# schematic.net
KiCad netlist of a schematic drawn in EAGLE
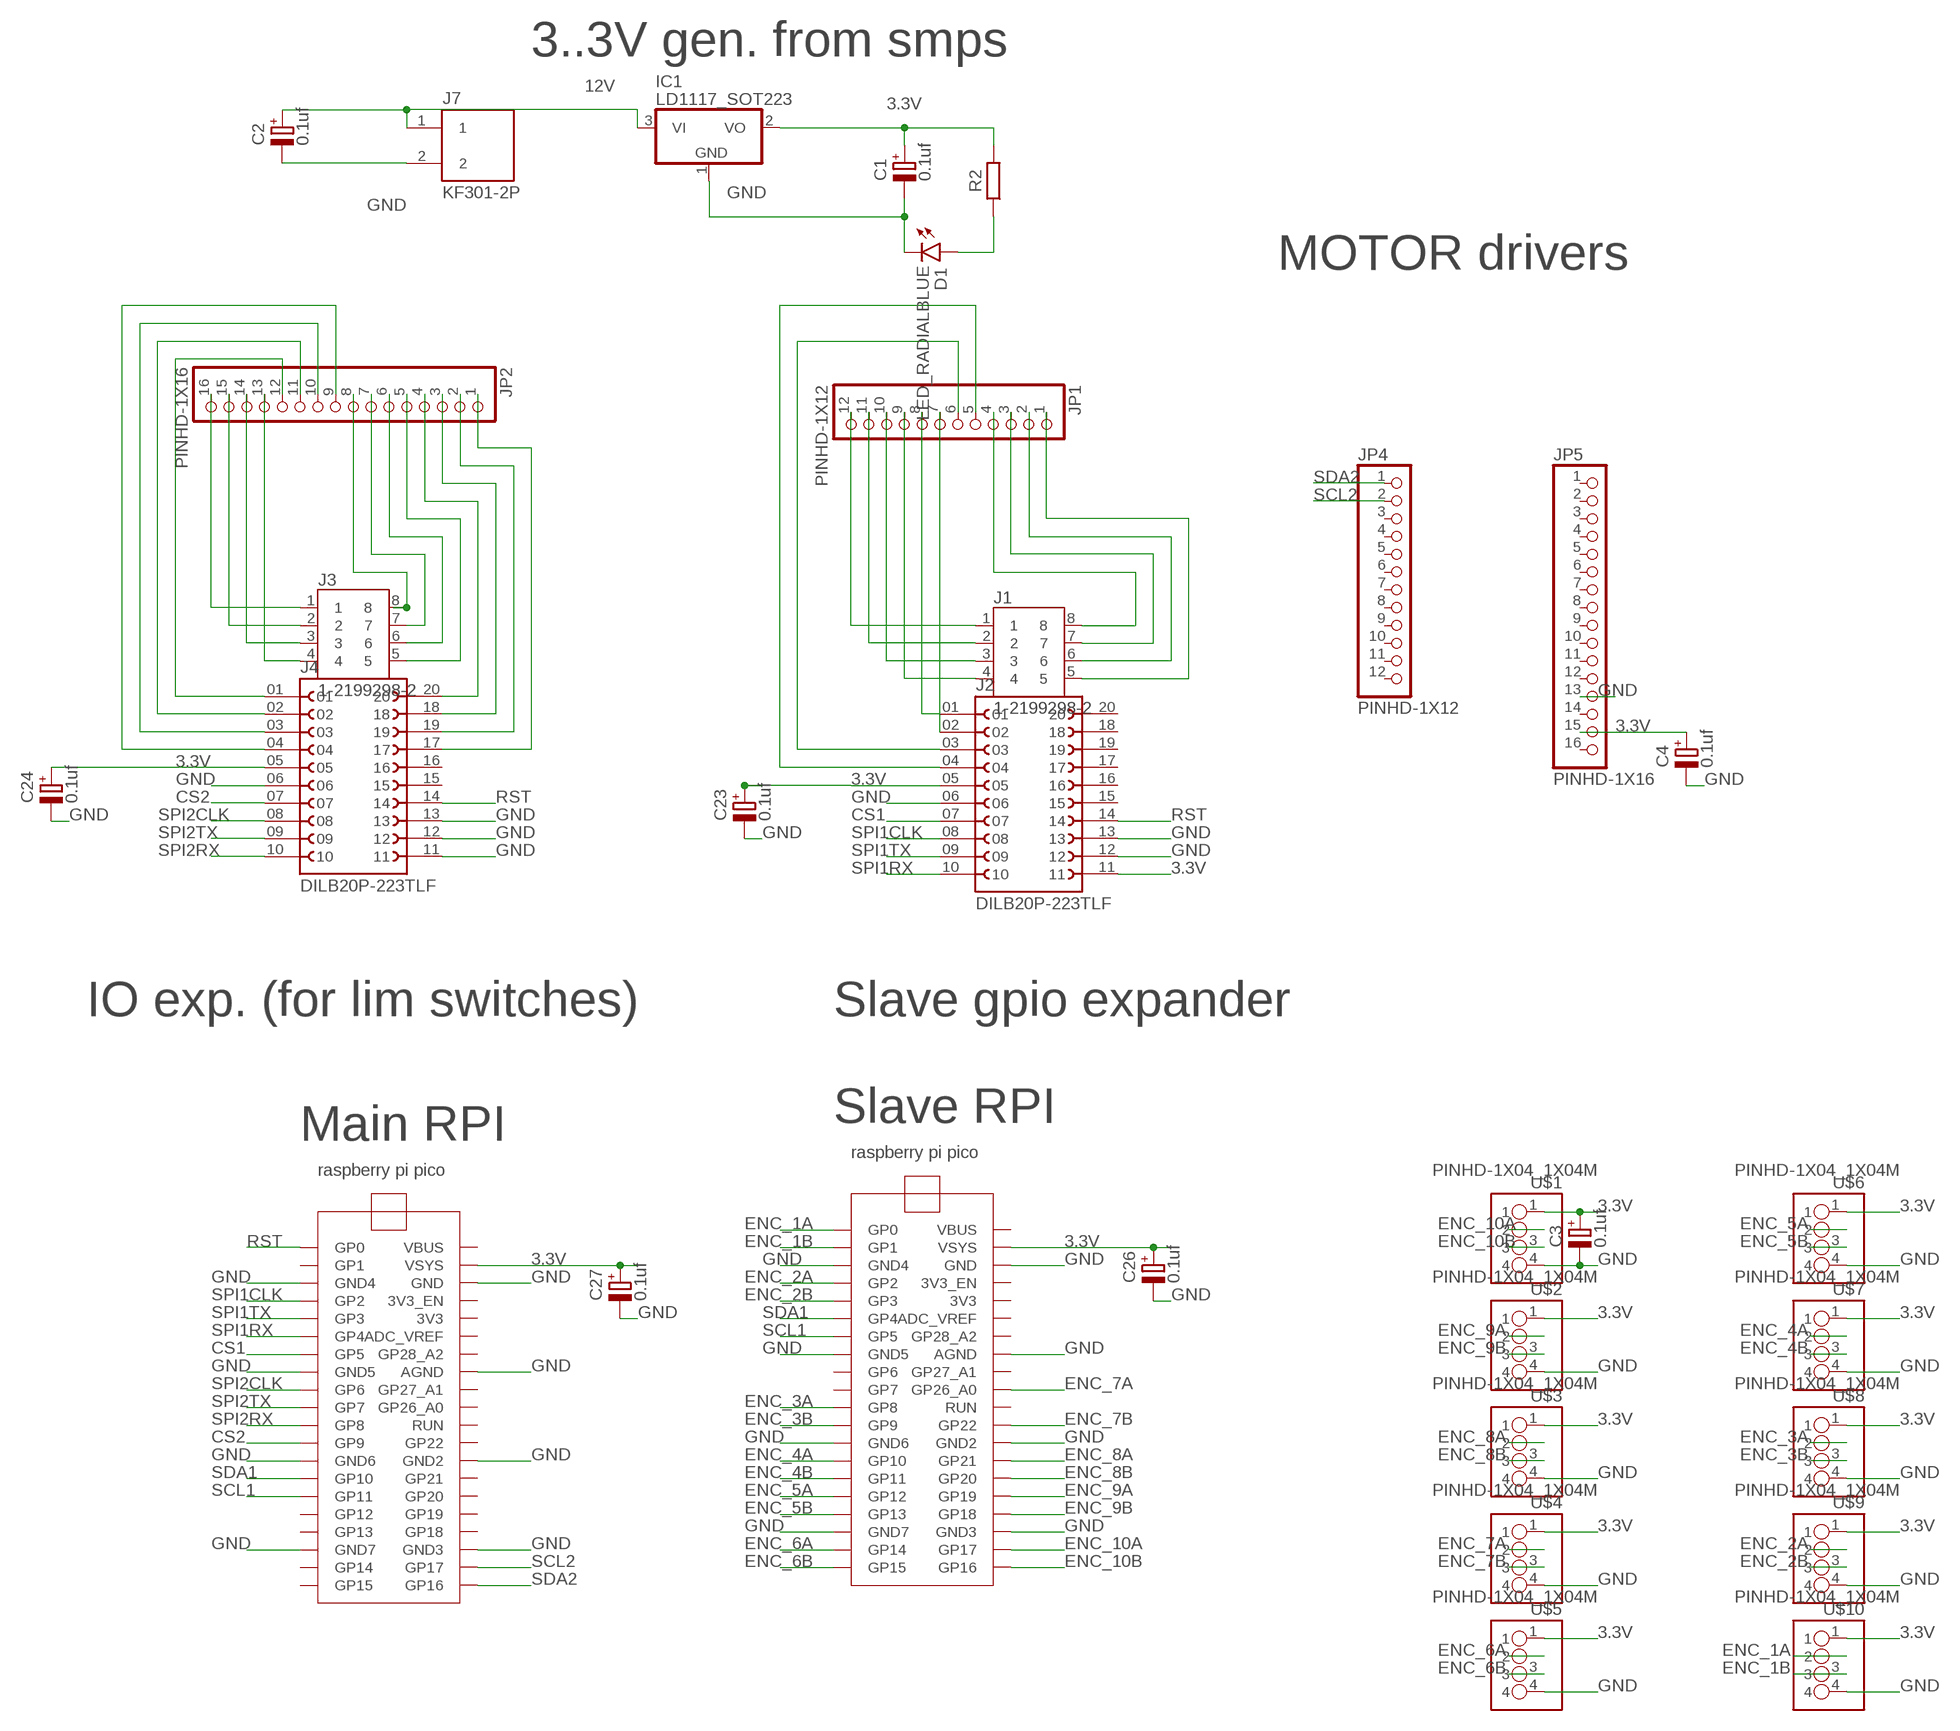
[diagram p0: schematic, sheet 1]

(export (version "E")
  (design (tool "Eeschema 10.0.6"))
  (components
    (comp (ref "C1")
      (value "0.1uf")
      (footprint "eagle-import:CAPPRD254W65D500H1150B")
      (libsource (lib "eagle-import") (part "CAPACITOR-POLRADIAL-5MM-DIA"))
    )
    (comp (ref "C2")
      (value "0.1uf")
      (footprint "eagle-import:CAPPRD254W65D500H1150B")
      (libsource (lib "eagle-import") (part "CAPACITOR-POLRADIAL-5MM-DIA"))
    )
    (comp (ref "C3")
      (value "0.1uf")
      (footprint "eagle-import:CAPPRD254W65D500H1150B")
      (libsource (lib "eagle-import") (part "CAPACITOR-POLRADIAL-5MM-DIA"))
    )
    (comp (ref "C4")
      (value "0.1uf")
      (footprint "eagle-import:CAPPRD254W65D500H1150B")
      (libsource (lib "eagle-import") (part "CAPACITOR-POLRADIAL-5MM-DIA"))
    )
    (comp (ref "C23")
      (value "0.1uf")
      (footprint "eagle-import:CAPPRD254W65D500H1150B")
      (libsource (lib "eagle-import") (part "CAPACITOR-POLRADIAL-5MM-DIA"))
    )
    (comp (ref "C24")
      (value "0.1uf")
      (footprint "eagle-import:CAPPRD254W65D500H1150B")
      (libsource (lib "eagle-import") (part "CAPACITOR-POLRADIAL-5MM-DIA"))
    )
    (comp (ref "C26")
      (value "0.1uf")
      (footprint "eagle-import:CAPPRD254W65D500H1150B")
      (libsource (lib "eagle-import") (part "CAPACITOR-POLRADIAL-5MM-DIA"))
    )
    (comp (ref "C27")
      (value "0.1uf")
      (footprint "eagle-import:CAPPRD254W65D500H1150B")
      (libsource (lib "eagle-import") (part "CAPACITOR-POLRADIAL-5MM-DIA"))
    )
    (comp (ref "D1")
      (value "LED_RADIALBLUE")
      (footprint "eagle-import:LEDRD254W60D565H860B_B")
      (libsource (lib "eagle-import") (part "LED_RADIALBLUE"))
    )
    (comp (ref "IC1")
      (value "LD1117_SOT223")
      (footprint "eagle-import:SOT230P700X170-4")
      (libsource (lib "eagle-import") (part "LD1117_SOT223"))
    )
    (comp (ref "J1")
      (value "1-2199298-2")
      (footprint "eagle-import:TE_1-2199298-2")
      (fields (field (name "MF") "TE Connectivity"))
      (libsource (lib "eagle-import") (part "1-2199298-2"))
    )
    (comp (ref "J2")
      (value "DILB20P-223TLF")
      (footprint "eagle-import:AMPHENOL_DILB20P-223TLF")
      (fields (field (name "MF") "FCI Connectors"))
      (libsource (lib "eagle-import") (part "DILB20P-223TLF"))
    )
    (comp (ref "J3")
      (value "1-2199298-2")
      (footprint "eagle-import:TE_1-2199298-2")
      (fields (field (name "MF") "TE Connectivity"))
      (libsource (lib "eagle-import") (part "1-2199298-2"))
    )
    (comp (ref "J4")
      (value "DILB20P-223TLF")
      (footprint "eagle-import:AMPHENOL_DILB20P-223TLF")
      (fields (field (name "MF") "FCI Connectors"))
      (libsource (lib "eagle-import") (part "DILB20P-223TLF"))
    )
    (comp (ref "J7")
      (value "KF301-2P")
      (footprint "eagle-import:HANDSON_KF301-2P")
      (fields (field (name "MF") "Handson Technology"))
      (libsource (lib "eagle-import") (part "KF301-2P"))
    )
    (comp (ref "JP1")
      (value "PINHD-1X12")
      (footprint "eagle-import:1X12")
      (fields (field (name "MANUFACTURER") "Generic"))
      (libsource (lib "eagle-import") (part "PINHD-1X12"))
    )
    (comp (ref "JP2")
      (value "PINHD-1X16")
      (footprint "eagle-import:1X16")
      (fields (field (name "MANUFACTURER") "Generic"))
      (libsource (lib "eagle-import") (part "PINHD-1X16"))
    )
    (comp (ref "JP4")
      (value "PINHD-1X12")
      (footprint "eagle-import:1X12")
      (fields (field (name "MANUFACTURER") "Generic"))
      (libsource (lib "eagle-import") (part "PINHD-1X12"))
    )
    (comp (ref "JP5")
      (value "PINHD-1X16")
      (footprint "eagle-import:1X16")
      (fields (field (name "MANUFACTURER") "Generic"))
      (libsource (lib "eagle-import") (part "PINHD-1X16"))
    )
    (comp (ref "R2")
      (value "R_AXIAL-11.7MM-PITCH")
      (footprint "eagle-import:RESAD1176W63L850D250B")
      (libsource (lib "eagle-import") (part "RAXIAL-11.7MM-PITCH_"))
    )
    (comp (ref "U$1")
      (value "PINHD-1X04_1X04M")
      (footprint "eagle-import:1X04")
      (libsource (lib "eagle-import") (part "PINHD-1X04_1X04M"))
    )
    (comp (ref "U$2")
      (value "PINHD-1X04_1X04M")
      (footprint "eagle-import:1X04")
      (libsource (lib "eagle-import") (part "PINHD-1X04_1X04M"))
    )
    (comp (ref "U$3")
      (value "PINHD-1X04_1X04M")
      (footprint "eagle-import:1X04")
      (libsource (lib "eagle-import") (part "PINHD-1X04_1X04M"))
    )
    (comp (ref "U$4")
      (value "PINHD-1X04_1X04M")
      (footprint "eagle-import:1X04")
      (libsource (lib "eagle-import") (part "PINHD-1X04_1X04M"))
    )
    (comp (ref "U$5")
      (value "PINHD-1X04_1X04M")
      (footprint "eagle-import:1X04")
      (libsource (lib "eagle-import") (part "PINHD-1X04_1X04M"))
    )
    (comp (ref "U$6")
      (value "PINHD-1X04_1X04M")
      (footprint "eagle-import:1X04")
      (libsource (lib "eagle-import") (part "PINHD-1X04_1X04M"))
    )
    (comp (ref "U$7")
      (value "PINHD-1X04_1X04M")
      (footprint "eagle-import:1X04")
      (libsource (lib "eagle-import") (part "PINHD-1X04_1X04M"))
    )
    (comp (ref "U$8")
      (value "PINHD-1X04_1X04M")
      (footprint "eagle-import:1X04")
      (libsource (lib "eagle-import") (part "PINHD-1X04_1X04M"))
    )
    (comp (ref "U$9")
      (value "PINHD-1X04_1X04M")
      (footprint "eagle-import:1X04")
      (libsource (lib "eagle-import") (part "PINHD-1X04_1X04M"))
    )
    (comp (ref "U$10")
      (value "PINHD-1X04_1X04M")
      (footprint "eagle-import:1X04")
      (libsource (lib "eagle-import") (part "PINHD-1X04_1X04M"))
    )
    (comp (ref "U2")
      (value "RASPBERRY_PI_PICO")
      (footprint "eagle-import:RASPBERRY_PI_PICO")
      (fields (field (name "MF") "Raspberry Pi") (field (name "MP") "RASPBERRY PI PICO"))
      (libsource (lib "eagle-import") (part "RASPBERRY_PI_PICO"))
    )
    (comp (ref "U3")
      (value "RASPBERRY_PI_PICO")
      (footprint "eagle-import:RASPBERRY_PI_PICO")
      (fields (field (name "MF") "Raspberry Pi") (field (name "MP") "RASPBERRY PI PICO"))
      (libsource (lib "eagle-import") (part "RASPBERRY_PI_PICO"))
    )
  )
  (nets
    (net (code "1") (name "/3.3V") (class "Default")
      (node (ref "C1") (pin "1") (pinfunction "+_1") (pintype "passive"))
      (node (ref "C23") (pin "1") (pinfunction "+_1") (pintype "passive"))
      (node (ref "C24") (pin "1") (pinfunction "+_1") (pintype "passive"))
      (node (ref "C26") (pin "1") (pinfunction "+_1") (pintype "passive"))
      (node (ref "C27") (pin "1") (pinfunction "+_1") (pintype "passive"))
      (node (ref "C3") (pin "1") (pinfunction "+_1") (pintype "passive"))
      (node (ref "C4") (pin "1") (pinfunction "+_1") (pintype "passive"))
      (node (ref "IC1") (pin "2") (pinfunction "VO_2") (pintype "passive"))
      (node (ref "J2") (pin "05") (pinfunction "05_05") (pintype "passive"))
      (node (ref "J2") (pin "11") (pinfunction "11_11") (pintype "passive"))
      (node (ref "J4") (pin "05") (pinfunction "05_05") (pintype "passive"))
      (node (ref "JP5") (pin "15") (pinfunction "15_15") (pintype "passive"))
      (node (ref "R2") (pin "2") (pinfunction "2_2") (pintype "passive"))
      (node (ref "U$1") (pin "1") (pinfunction "1_1") (pintype "bidirectional"))
      (node (ref "U$10") (pin "1") (pinfunction "1_1") (pintype "bidirectional"))
      (node (ref "U$2") (pin "1") (pinfunction "1_1") (pintype "bidirectional"))
      (node (ref "U$3") (pin "1") (pinfunction "1_1") (pintype "bidirectional"))
      (node (ref "U$4") (pin "1") (pinfunction "1_1") (pintype "bidirectional"))
      (node (ref "U$5") (pin "1") (pinfunction "1_1") (pintype "bidirectional"))
      (node (ref "U$6") (pin "1") (pinfunction "1_1") (pintype "bidirectional"))
      (node (ref "U$7") (pin "1") (pinfunction "1_1") (pintype "bidirectional"))
      (node (ref "U$8") (pin "1") (pinfunction "1_1") (pintype "bidirectional"))
      (node (ref "U$9") (pin "1") (pinfunction "1_1") (pintype "bidirectional"))
      (node (ref "U2") (pin "VSYS") (pinfunction "VSYS_VSYS") (pintype "bidirectional"))
      (node (ref "U3") (pin "VSYS") (pinfunction "VSYS_VSYS") (pintype "bidirectional"))
    )
    (net (code "2") (name "/12V") (class "Default")
      (node (ref "C2") (pin "1") (pinfunction "+_1") (pintype "passive"))
      (node (ref "IC1") (pin "3") (pinfunction "VI_3") (pintype "input"))
      (node (ref "J7") (pin "1") (pinfunction "1_1") (pintype "passive"))
    )
    (net (code "3") (name "/CS1") (class "Default")
      (node (ref "J2") (pin "07") (pinfunction "07_07") (pintype "passive"))
      (node (ref "U2") (pin "GP5") (pinfunction "GP5_GP5") (pintype "bidirectional"))
    )
    (net (code "4") (name "/CS2") (class "Default")
      (node (ref "J4") (pin "07") (pinfunction "07_07") (pintype "passive"))
      (node (ref "U2") (pin "GP9") (pinfunction "GP9_GP9") (pintype "bidirectional"))
    )
    (net (code "5") (name "/ENC_1A") (class "Default")
      (node (ref "U$10") (pin "2") (pinfunction "2_2") (pintype "bidirectional"))
      (node (ref "U3") (pin "GP0") (pinfunction "GP0_GP0") (pintype "bidirectional"))
    )
    (net (code "6") (name "/ENC_1B") (class "Default")
      (node (ref "U$10") (pin "3") (pinfunction "3_3") (pintype "bidirectional"))
      (node (ref "U3") (pin "GP1") (pinfunction "GP1_GP1") (pintype "bidirectional"))
    )
    (net (code "7") (name "/ENC_2A") (class "Default")
      (node (ref "U$9") (pin "2") (pinfunction "2_2") (pintype "bidirectional"))
      (node (ref "U3") (pin "GP2") (pinfunction "GP2_GP2") (pintype "bidirectional"))
    )
    (net (code "8") (name "/ENC_2B") (class "Default")
      (node (ref "U$9") (pin "3") (pinfunction "3_3") (pintype "bidirectional"))
      (node (ref "U3") (pin "GP3") (pinfunction "GP3_GP3") (pintype "bidirectional"))
    )
    (net (code "9") (name "/ENC_3A") (class "Default")
      (node (ref "U$8") (pin "2") (pinfunction "2_2") (pintype "bidirectional"))
      (node (ref "U3") (pin "GP8") (pinfunction "GP8_GP8") (pintype "bidirectional"))
    )
    (net (code "10") (name "/ENC_3B") (class "Default")
      (node (ref "U$8") (pin "3") (pinfunction "3_3") (pintype "bidirectional"))
      (node (ref "U3") (pin "GP9") (pinfunction "GP9_GP9") (pintype "bidirectional"))
    )
    (net (code "11") (name "/ENC_4A") (class "Default")
      (node (ref "U$7") (pin "2") (pinfunction "2_2") (pintype "bidirectional"))
      (node (ref "U3") (pin "GP10") (pinfunction "GP10_GP10") (pintype "bidirectional"))
    )
    (net (code "12") (name "/ENC_4B") (class "Default")
      (node (ref "U$7") (pin "3") (pinfunction "3_3") (pintype "bidirectional"))
      (node (ref "U3") (pin "GP11") (pinfunction "GP11_GP11") (pintype "bidirectional"))
    )
    (net (code "13") (name "/ENC_5A") (class "Default")
      (node (ref "U$6") (pin "2") (pinfunction "2_2") (pintype "bidirectional"))
      (node (ref "U3") (pin "GP12") (pinfunction "GP12_GP12") (pintype "bidirectional"))
    )
    (net (code "14") (name "/ENC_5B") (class "Default")
      (node (ref "U$6") (pin "3") (pinfunction "3_3") (pintype "bidirectional"))
      (node (ref "U3") (pin "GP13") (pinfunction "GP13_GP13") (pintype "bidirectional"))
    )
    (net (code "15") (name "/ENC_6A") (class "Default")
      (node (ref "U$5") (pin "2") (pinfunction "2_2") (pintype "bidirectional"))
      (node (ref "U3") (pin "GP14") (pinfunction "GP14_GP14") (pintype "bidirectional"))
    )
    (net (code "16") (name "/ENC_6B") (class "Default")
      (node (ref "U$5") (pin "3") (pinfunction "3_3") (pintype "bidirectional"))
      (node (ref "U3") (pin "GP15") (pinfunction "GP15_GP15") (pintype "bidirectional"))
    )
    (net (code "17") (name "/ENC_7A") (class "Default")
      (node (ref "U$4") (pin "2") (pinfunction "2_2") (pintype "bidirectional"))
      (node (ref "U3") (pin "GP26_A0") (pinfunction "GP26_A0_GP26_A0") (pintype "bidirectional"))
    )
    (net (code "18") (name "/ENC_7B") (class "Default")
      (node (ref "U$4") (pin "3") (pinfunction "3_3") (pintype "bidirectional"))
      (node (ref "U3") (pin "GP22") (pinfunction "GP22_GP22") (pintype "bidirectional"))
    )
    (net (code "19") (name "/ENC_8A") (class "Default")
      (node (ref "U$3") (pin "2") (pinfunction "2_2") (pintype "bidirectional"))
      (node (ref "U3") (pin "GP21") (pinfunction "GP21_GP21") (pintype "bidirectional"))
    )
    (net (code "20") (name "/ENC_8B") (class "Default")
      (node (ref "U$3") (pin "3") (pinfunction "3_3") (pintype "bidirectional"))
      (node (ref "U3") (pin "GP20") (pinfunction "GP20_GP20") (pintype "bidirectional"))
    )
    (net (code "21") (name "/ENC_9A") (class "Default")
      (node (ref "U$2") (pin "2") (pinfunction "2_2") (pintype "bidirectional"))
      (node (ref "U3") (pin "GP19") (pinfunction "GP19_GP19") (pintype "bidirectional"))
    )
    (net (code "22") (name "/ENC_9B") (class "Default")
      (node (ref "U$2") (pin "3") (pinfunction "3_3") (pintype "bidirectional"))
      (node (ref "U3") (pin "GP18") (pinfunction "GP18_GP18") (pintype "bidirectional"))
    )
    (net (code "23") (name "/ENC_10A") (class "Default")
      (node (ref "U$1") (pin "2") (pinfunction "2_2") (pintype "bidirectional"))
      (node (ref "U3") (pin "GP17") (pinfunction "GP17_GP17") (pintype "bidirectional"))
    )
    (net (code "24") (name "/ENC_10B") (class "Default")
      (node (ref "U$1") (pin "3") (pinfunction "3_3") (pintype "bidirectional"))
      (node (ref "U3") (pin "GP16") (pinfunction "GP16_GP16") (pintype "bidirectional"))
    )
    (net (code "25") (name "/GND") (class "Default")
      (node (ref "C1") (pin "2") (pinfunction "-_2") (pintype "passive"))
      (node (ref "C2") (pin "2") (pinfunction "-_2") (pintype "passive"))
      (node (ref "C23") (pin "2") (pinfunction "-_2") (pintype "passive"))
      (node (ref "C24") (pin "2") (pinfunction "-_2") (pintype "passive"))
      (node (ref "C26") (pin "2") (pinfunction "-_2") (pintype "passive"))
      (node (ref "C27") (pin "2") (pinfunction "-_2") (pintype "passive"))
      (node (ref "C3") (pin "2") (pinfunction "-_2") (pintype "passive"))
      (node (ref "C4") (pin "2") (pinfunction "-_2") (pintype "passive"))
      (node (ref "D1") (pin "C") (pinfunction "C_C") (pintype "passive"))
      (node (ref "IC1") (pin "1") (pinfunction "GND_1") (pintype "passive"))
      (node (ref "J2") (pin "06") (pinfunction "06_06") (pintype "passive"))
      (node (ref "J2") (pin "12") (pinfunction "12_12") (pintype "passive"))
      (node (ref "J2") (pin "13") (pinfunction "13_13") (pintype "passive"))
      (node (ref "J4") (pin "06") (pinfunction "06_06") (pintype "passive"))
      (node (ref "J4") (pin "11") (pinfunction "11_11") (pintype "passive"))
      (node (ref "J4") (pin "12") (pinfunction "12_12") (pintype "passive"))
      (node (ref "J4") (pin "13") (pinfunction "13_13") (pintype "passive"))
      (node (ref "J7") (pin "2") (pinfunction "2_2") (pintype "passive"))
      (node (ref "JP5") (pin "13") (pinfunction "13_13") (pintype "passive"))
      (node (ref "U$1") (pin "4") (pinfunction "4_4") (pintype "bidirectional"))
      (node (ref "U$10") (pin "4") (pinfunction "4_4") (pintype "bidirectional"))
      (node (ref "U$2") (pin "4") (pinfunction "4_4") (pintype "bidirectional"))
      (node (ref "U$3") (pin "4") (pinfunction "4_4") (pintype "bidirectional"))
      (node (ref "U$4") (pin "4") (pinfunction "4_4") (pintype "bidirectional"))
      (node (ref "U$5") (pin "4") (pinfunction "4_4") (pintype "bidirectional"))
      (node (ref "U$6") (pin "4") (pinfunction "4_4") (pintype "bidirectional"))
      (node (ref "U$7") (pin "4") (pinfunction "4_4") (pintype "bidirectional"))
      (node (ref "U$8") (pin "4") (pinfunction "4_4") (pintype "bidirectional"))
      (node (ref "U$9") (pin "4") (pinfunction "4_4") (pintype "bidirectional"))
      (node (ref "U2") (pin "AGND") (pinfunction "AGND_AGND") (pintype "bidirectional"))
      (node (ref "U2") (pin "GND") (pinfunction "GND_GND") (pintype "bidirectional"))
      (node (ref "U2") (pin "GND2") (pinfunction "GND2_GND2") (pintype "bidirectional"))
      (node (ref "U2") (pin "GND3") (pinfunction "GND3_GND3") (pintype "bidirectional"))
      (node (ref "U2") (pin "GND4") (pinfunction "GND4_GND4") (pintype "bidirectional"))
      (node (ref "U2") (pin "GND5") (pinfunction "GND5_GND5") (pintype "bidirectional"))
      (node (ref "U2") (pin "GND6") (pinfunction "GND6_GND6") (pintype "bidirectional"))
      (node (ref "U2") (pin "GND7") (pinfunction "GND7_GND7") (pintype "bidirectional"))
      (node (ref "U3") (pin "AGND") (pinfunction "AGND_AGND") (pintype "bidirectional"))
      (node (ref "U3") (pin "GND") (pinfunction "GND_GND") (pintype "bidirectional"))
      (node (ref "U3") (pin "GND2") (pinfunction "GND2_GND2") (pintype "bidirectional"))
      (node (ref "U3") (pin "GND3") (pinfunction "GND3_GND3") (pintype "bidirectional"))
      (node (ref "U3") (pin "GND4") (pinfunction "GND4_GND4") (pintype "bidirectional"))
      (node (ref "U3") (pin "GND5") (pinfunction "GND5_GND5") (pintype "bidirectional"))
      (node (ref "U3") (pin "GND6") (pinfunction "GND6_GND6") (pintype "bidirectional"))
      (node (ref "U3") (pin "GND7") (pinfunction "GND7_GND7") (pintype "bidirectional"))
    )
    (net (code "26") (name "/RST") (class "Default")
      (node (ref "J2") (pin "14") (pinfunction "14_14") (pintype "passive"))
      (node (ref "J4") (pin "14") (pinfunction "14_14") (pintype "passive"))
      (node (ref "U2") (pin "GP0") (pinfunction "GP0_GP0") (pintype "bidirectional"))
    )
    (net (code "27") (name "/SCL1") (class "Default")
      (node (ref "U2") (pin "GP11") (pinfunction "GP11_GP11") (pintype "bidirectional"))
      (node (ref "U3") (pin "GP5") (pinfunction "GP5_GP5") (pintype "bidirectional"))
    )
    (net (code "28") (name "/SCL2") (class "Default")
      (node (ref "JP4") (pin "2") (pinfunction "2_2") (pintype "passive"))
      (node (ref "U2") (pin "GP17") (pinfunction "GP17_GP17") (pintype "bidirectional"))
    )
    (net (code "29") (name "/SDA1") (class "Default")
      (node (ref "U2") (pin "GP10") (pinfunction "GP10_GP10") (pintype "bidirectional"))
      (node (ref "U3") (pin "GP4") (pinfunction "GP4_GP4") (pintype "bidirectional"))
    )
    (net (code "30") (name "/SDA2") (class "Default")
      (node (ref "JP4") (pin "1") (pinfunction "1_1") (pintype "passive"))
      (node (ref "U2") (pin "GP16") (pinfunction "GP16_GP16") (pintype "bidirectional"))
    )
    (net (code "31") (name "/SPI1CLK") (class "Default")
      (node (ref "J2") (pin "08") (pinfunction "08_08") (pintype "passive"))
      (node (ref "U2") (pin "GP2") (pinfunction "GP2_GP2") (pintype "bidirectional"))
    )
    (net (code "32") (name "/SPI1RX") (class "Default")
      (node (ref "J2") (pin "10") (pinfunction "10_10") (pintype "passive"))
      (node (ref "U2") (pin "GP4") (pinfunction "GP4_GP4") (pintype "bidirectional"))
    )
    (net (code "33") (name "/SPI1TX") (class "Default")
      (node (ref "J2") (pin "09") (pinfunction "09_09") (pintype "passive"))
      (node (ref "U2") (pin "GP3") (pinfunction "GP3_GP3") (pintype "bidirectional"))
    )
    (net (code "34") (name "/SPI2CLK") (class "Default")
      (node (ref "J4") (pin "08") (pinfunction "08_08") (pintype "passive"))
      (node (ref "U2") (pin "GP6") (pinfunction "GP6_GP6") (pintype "bidirectional"))
    )
    (net (code "35") (name "/SPI2RX") (class "Default")
      (node (ref "J4") (pin "10") (pinfunction "10_10") (pintype "passive"))
      (node (ref "U2") (pin "GP8") (pinfunction "GP8_GP8") (pintype "bidirectional"))
    )
    (net (code "36") (name "/SPI2TX") (class "Default")
      (node (ref "J4") (pin "09") (pinfunction "09_09") (pintype "passive"))
      (node (ref "U2") (pin "GP7") (pinfunction "GP7_GP7") (pintype "bidirectional"))
    )
    (net (code "37") (name "Net-(D1-PadA)") (class "Default")
      (node (ref "D1") (pin "A") (pinfunction "A_A") (pintype "passive"))
      (node (ref "R2") (pin "1") (pinfunction "1_1") (pintype "passive"))
    )
    (net (code "38") (name "Net-(J1-Pad1)") (class "Default")
      (node (ref "J1") (pin "1") (pinfunction "1_1") (pintype "passive"))
      (node (ref "JP1") (pin "12") (pinfunction "12_12") (pintype "passive"))
    )
    (net (code "39") (name "Net-(J1-Pad2)") (class "Default")
      (node (ref "J1") (pin "2") (pinfunction "2_2") (pintype "passive"))
      (node (ref "JP1") (pin "11") (pinfunction "11_11") (pintype "passive"))
    )
    (net (code "40") (name "Net-(J1-Pad3)") (class "Default")
      (node (ref "J1") (pin "3") (pinfunction "3_3") (pintype "passive"))
      (node (ref "JP1") (pin "10") (pinfunction "10_10") (pintype "passive"))
    )
    (net (code "41") (name "Net-(J1-Pad4)") (class "Default")
      (node (ref "J1") (pin "4") (pinfunction "4_4") (pintype "passive"))
      (node (ref "JP1") (pin "9") (pinfunction "9_9") (pintype "passive"))
    )
    (net (code "42") (name "Net-(J1-Pad5)") (class "Default")
      (node (ref "J1") (pin "5") (pinfunction "5_5") (pintype "passive"))
      (node (ref "JP1") (pin "1") (pinfunction "1_1") (pintype "passive"))
    )
    (net (code "43") (name "Net-(J1-Pad6)") (class "Default")
      (node (ref "J1") (pin "6") (pinfunction "6_6") (pintype "passive"))
      (node (ref "JP1") (pin "2") (pinfunction "2_2") (pintype "passive"))
    )
    (net (code "44") (name "Net-(J1-Pad7)") (class "Default")
      (node (ref "J1") (pin "7") (pinfunction "7_7") (pintype "passive"))
      (node (ref "JP1") (pin "3") (pinfunction "3_3") (pintype "passive"))
    )
    (net (code "45") (name "Net-(J1-Pad8)") (class "Default")
      (node (ref "J1") (pin "8") (pinfunction "8_8") (pintype "passive"))
      (node (ref "JP1") (pin "4") (pinfunction "4_4") (pintype "passive"))
    )
    (net (code "46") (name "Net-(J2-Pad01)") (class "Default")
      (node (ref "J2") (pin "01") (pinfunction "01_01") (pintype "passive"))
      (node (ref "JP1") (pin "8") (pinfunction "8_8") (pintype "passive"))
    )
    (net (code "47") (name "Net-(J2-Pad02)") (class "Default")
      (node (ref "J2") (pin "02") (pinfunction "02_02") (pintype "passive"))
      (node (ref "JP1") (pin "7") (pinfunction "7_7") (pintype "passive"))
    )
    (net (code "48") (name "Net-(J2-Pad03)") (class "Default")
      (node (ref "J2") (pin "03") (pinfunction "03_03") (pintype "passive"))
      (node (ref "JP1") (pin "6") (pinfunction "6_6") (pintype "passive"))
    )
    (net (code "49") (name "Net-(J2-Pad04)") (class "Default")
      (node (ref "J2") (pin "04") (pinfunction "04_04") (pintype "passive"))
      (node (ref "JP1") (pin "5") (pinfunction "5_5") (pintype "passive"))
    )
    (net (code "50") (name "Net-(J3-Pad1)") (class "Default")
      (node (ref "J3") (pin "1") (pinfunction "1_1") (pintype "passive"))
      (node (ref "JP2") (pin "16") (pinfunction "16_16") (pintype "passive"))
    )
    (net (code "51") (name "Net-(J3-Pad2)") (class "Default")
      (node (ref "J3") (pin "2") (pinfunction "2_2") (pintype "passive"))
      (node (ref "JP2") (pin "15") (pinfunction "15_15") (pintype "passive"))
    )
    (net (code "52") (name "Net-(J3-Pad3)") (class "Default")
      (node (ref "J3") (pin "3") (pinfunction "3_3") (pintype "passive"))
      (node (ref "JP2") (pin "14") (pinfunction "14_14") (pintype "passive"))
    )
    (net (code "53") (name "Net-(J3-Pad4)") (class "Default")
      (node (ref "J3") (pin "4") (pinfunction "4_4") (pintype "passive"))
      (node (ref "JP2") (pin "13") (pinfunction "13_13") (pintype "passive"))
    )
    (net (code "54") (name "Net-(J3-Pad5)") (class "Default")
      (node (ref "J3") (pin "5") (pinfunction "5_5") (pintype "passive"))
      (node (ref "JP2") (pin "5") (pinfunction "5_5") (pintype "passive"))
    )
    (net (code "55") (name "Net-(J3-Pad6)") (class "Default")
      (node (ref "J3") (pin "6") (pinfunction "6_6") (pintype "passive"))
      (node (ref "JP2") (pin "6") (pinfunction "6_6") (pintype "passive"))
    )
    (net (code "56") (name "Net-(J3-Pad7)") (class "Default")
      (node (ref "J3") (pin "7") (pinfunction "7_7") (pintype "passive"))
      (node (ref "JP2") (pin "7") (pinfunction "7_7") (pintype "passive"))
    )
    (net (code "57") (name "Net-(J3-Pad8)") (class "Default")
      (node (ref "J3") (pin "8") (pinfunction "8_8") (pintype "passive"))
      (node (ref "JP2") (pin "8") (pinfunction "8_8") (pintype "passive"))
    )
    (net (code "58") (name "Net-(J4-Pad01)") (class "Default")
      (node (ref "J4") (pin "01") (pinfunction "01_01") (pintype "passive"))
      (node (ref "JP2") (pin "12") (pinfunction "12_12") (pintype "passive"))
    )
    (net (code "59") (name "Net-(J4-Pad02)") (class "Default")
      (node (ref "J4") (pin "02") (pinfunction "02_02") (pintype "passive"))
      (node (ref "JP2") (pin "11") (pinfunction "11_11") (pintype "passive"))
    )
    (net (code "60") (name "Net-(J4-Pad03)") (class "Default")
      (node (ref "J4") (pin "03") (pinfunction "03_03") (pintype "passive"))
      (node (ref "JP2") (pin "10") (pinfunction "10_10") (pintype "passive"))
    )
    (net (code "61") (name "Net-(J4-Pad04)") (class "Default")
      (node (ref "J4") (pin "04") (pinfunction "04_04") (pintype "passive"))
      (node (ref "JP2") (pin "9") (pinfunction "9_9") (pintype "passive"))
    )
    (net (code "62") (name "Net-(J4-Pad17)") (class "Default")
      (node (ref "J4") (pin "17") (pinfunction "17_17") (pintype "passive"))
      (node (ref "JP2") (pin "1") (pinfunction "1_1") (pintype "passive"))
    )
    (net (code "63") (name "Net-(J4-Pad18)") (class "Default")
      (node (ref "J4") (pin "18") (pinfunction "18_18") (pintype "passive"))
      (node (ref "JP2") (pin "3") (pinfunction "3_3") (pintype "passive"))
    )
    (net (code "64") (name "Net-(J4-Pad19)") (class "Default")
      (node (ref "J4") (pin "19") (pinfunction "19_19") (pintype "passive"))
      (node (ref "JP2") (pin "2") (pinfunction "2_2") (pintype "passive"))
    )
    (net (code "65") (name "Net-(J4-Pad20)") (class "Default")
      (node (ref "J4") (pin "20") (pinfunction "20_20") (pintype "passive"))
      (node (ref "JP2") (pin "4") (pinfunction "4_4") (pintype "passive"))
    )
    (net (code "66") (name "unconnected-(J2-Pad15)") (class "Default")
      (node (ref "J2") (pin "15") (pinfunction "15_15") (pintype "passive"))
    )
    (net (code "67") (name "unconnected-(J2-Pad16)") (class "Default")
      (node (ref "J2") (pin "16") (pinfunction "16_16") (pintype "passive"))
    )
    (net (code "68") (name "unconnected-(J2-Pad17)") (class "Default")
      (node (ref "J2") (pin "17") (pinfunction "17_17") (pintype "passive"))
    )
    (net (code "69") (name "unconnected-(J2-Pad18)") (class "Default")
      (node (ref "J2") (pin "18") (pinfunction "18_18") (pintype "passive"))
    )
    (net (code "70") (name "unconnected-(J2-Pad19)") (class "Default")
      (node (ref "J2") (pin "19") (pinfunction "19_19") (pintype "passive"))
    )
    (net (code "71") (name "unconnected-(J2-Pad20)") (class "Default")
      (node (ref "J2") (pin "20") (pinfunction "20_20") (pintype "passive"))
    )
    (net (code "72") (name "unconnected-(J4-Pad15)") (class "Default")
      (node (ref "J4") (pin "15") (pinfunction "15_15") (pintype "passive"))
    )
    (net (code "73") (name "unconnected-(J4-Pad16)") (class "Default")
      (node (ref "J4") (pin "16") (pinfunction "16_16") (pintype "passive"))
    )
    (net (code "74") (name "unconnected-(JP4-Pad3)") (class "Default")
      (node (ref "JP4") (pin "3") (pinfunction "3_3") (pintype "passive"))
    )
    (net (code "75") (name "unconnected-(JP4-Pad4)") (class "Default")
      (node (ref "JP4") (pin "4") (pinfunction "4_4") (pintype "passive"))
    )
    (net (code "76") (name "unconnected-(JP4-Pad5)") (class "Default")
      (node (ref "JP4") (pin "5") (pinfunction "5_5") (pintype "passive"))
    )
    (net (code "77") (name "unconnected-(JP4-Pad6)") (class "Default")
      (node (ref "JP4") (pin "6") (pinfunction "6_6") (pintype "passive"))
    )
    (net (code "78") (name "unconnected-(JP4-Pad7)") (class "Default")
      (node (ref "JP4") (pin "7") (pinfunction "7_7") (pintype "passive"))
    )
    (net (code "79") (name "unconnected-(JP4-Pad8)") (class "Default")
      (node (ref "JP4") (pin "8") (pinfunction "8_8") (pintype "passive"))
    )
    (net (code "80") (name "unconnected-(JP4-Pad9)") (class "Default")
      (node (ref "JP4") (pin "9") (pinfunction "9_9") (pintype "passive"))
    )
    (net (code "81") (name "unconnected-(JP4-Pad10)") (class "Default")
      (node (ref "JP4") (pin "10") (pinfunction "10_10") (pintype "passive"))
    )
    (net (code "82") (name "unconnected-(JP4-Pad11)") (class "Default")
      (node (ref "JP4") (pin "11") (pinfunction "11_11") (pintype "passive"))
    )
    (net (code "83") (name "unconnected-(JP4-Pad12)") (class "Default")
      (node (ref "JP4") (pin "12") (pinfunction "12_12") (pintype "passive"))
    )
    (net (code "84") (name "unconnected-(JP5-Pad1)") (class "Default")
      (node (ref "JP5") (pin "1") (pinfunction "1_1") (pintype "passive"))
    )
    (net (code "85") (name "unconnected-(JP5-Pad2)") (class "Default")
      (node (ref "JP5") (pin "2") (pinfunction "2_2") (pintype "passive"))
    )
    (net (code "86") (name "unconnected-(JP5-Pad3)") (class "Default")
      (node (ref "JP5") (pin "3") (pinfunction "3_3") (pintype "passive"))
    )
    (net (code "87") (name "unconnected-(JP5-Pad4)") (class "Default")
      (node (ref "JP5") (pin "4") (pinfunction "4_4") (pintype "passive"))
    )
    (net (code "88") (name "unconnected-(JP5-Pad5)") (class "Default")
      (node (ref "JP5") (pin "5") (pinfunction "5_5") (pintype "passive"))
    )
    (net (code "89") (name "unconnected-(JP5-Pad6)") (class "Default")
      (node (ref "JP5") (pin "6") (pinfunction "6_6") (pintype "passive"))
    )
    (net (code "90") (name "unconnected-(JP5-Pad7)") (class "Default")
      (node (ref "JP5") (pin "7") (pinfunction "7_7") (pintype "passive"))
    )
    (net (code "91") (name "unconnected-(JP5-Pad8)") (class "Default")
      (node (ref "JP5") (pin "8") (pinfunction "8_8") (pintype "passive"))
    )
    (net (code "92") (name "unconnected-(JP5-Pad9)") (class "Default")
      (node (ref "JP5") (pin "9") (pinfunction "9_9") (pintype "passive"))
    )
    (net (code "93") (name "unconnected-(JP5-Pad10)") (class "Default")
      (node (ref "JP5") (pin "10") (pinfunction "10_10") (pintype "passive"))
    )
    (net (code "94") (name "unconnected-(JP5-Pad11)") (class "Default")
      (node (ref "JP5") (pin "11") (pinfunction "11_11") (pintype "passive"))
    )
    (net (code "95") (name "unconnected-(JP5-Pad12)") (class "Default")
      (node (ref "JP5") (pin "12") (pinfunction "12_12") (pintype "passive"))
    )
    (net (code "96") (name "unconnected-(JP5-Pad14)") (class "Default")
      (node (ref "JP5") (pin "14") (pinfunction "14_14") (pintype "passive"))
    )
    (net (code "97") (name "unconnected-(JP5-Pad16)") (class "Default")
      (node (ref "JP5") (pin "16") (pinfunction "16_16") (pintype "passive"))
    )
    (net (code "98") (name "unconnected-(U2-Pad3V3)") (class "Default")
      (node (ref "U2") (pin "3V3") (pinfunction "3V3_3V3") (pintype "bidirectional"))
    )
    (net (code "99") (name "unconnected-(U2-Pad3V3_EN)") (class "Default")
      (node (ref "U2") (pin "3V3_EN") (pinfunction "3V3_EN_3V3_EN") (pintype "bidirectional"))
    )
    (net (code "100") (name "unconnected-(U2-PadADC_VREF)") (class "Default")
      (node (ref "U2") (pin "ADC_VREF") (pinfunction "ADC_VREF_ADC_VREF") (pintype "bidirectional"))
    )
    (net (code "101") (name "unconnected-(U2-PadGP1)") (class "Default")
      (node (ref "U2") (pin "GP1") (pinfunction "GP1_GP1") (pintype "bidirectional"))
    )
    (net (code "102") (name "unconnected-(U2-PadGP12)") (class "Default")
      (node (ref "U2") (pin "GP12") (pinfunction "GP12_GP12") (pintype "bidirectional"))
    )
    (net (code "103") (name "unconnected-(U2-PadGP13)") (class "Default")
      (node (ref "U2") (pin "GP13") (pinfunction "GP13_GP13") (pintype "bidirectional"))
    )
    (net (code "104") (name "unconnected-(U2-PadGP14)") (class "Default")
      (node (ref "U2") (pin "GP14") (pinfunction "GP14_GP14") (pintype "bidirectional"))
    )
    (net (code "105") (name "unconnected-(U2-PadGP15)") (class "Default")
      (node (ref "U2") (pin "GP15") (pinfunction "GP15_GP15") (pintype "bidirectional"))
    )
    (net (code "106") (name "unconnected-(U2-PadGP18)") (class "Default")
      (node (ref "U2") (pin "GP18") (pinfunction "GP18_GP18") (pintype "bidirectional"))
    )
    (net (code "107") (name "unconnected-(U2-PadGP19)") (class "Default")
      (node (ref "U2") (pin "GP19") (pinfunction "GP19_GP19") (pintype "bidirectional"))
    )
    (net (code "108") (name "unconnected-(U2-PadGP20)") (class "Default")
      (node (ref "U2") (pin "GP20") (pinfunction "GP20_GP20") (pintype "bidirectional"))
    )
    (net (code "109") (name "unconnected-(U2-PadGP21)") (class "Default")
      (node (ref "U2") (pin "GP21") (pinfunction "GP21_GP21") (pintype "bidirectional"))
    )
    (net (code "110") (name "unconnected-(U2-PadGP22)") (class "Default")
      (node (ref "U2") (pin "GP22") (pinfunction "GP22_GP22") (pintype "bidirectional"))
    )
    (net (code "111") (name "unconnected-(U2-PadGP26_A0)") (class "Default")
      (node (ref "U2") (pin "GP26_A0") (pinfunction "GP26_A0_GP26_A0") (pintype "bidirectional"))
    )
    (net (code "112") (name "unconnected-(U2-PadGP27_A1)") (class "Default")
      (node (ref "U2") (pin "GP27_A1") (pinfunction "GP27_A1_GP27_A1") (pintype "bidirectional"))
    )
    (net (code "113") (name "unconnected-(U2-PadGP28_A2)") (class "Default")
      (node (ref "U2") (pin "GP28_A2") (pinfunction "GP28_A2_GP28_A2") (pintype "bidirectional"))
    )
    (net (code "114") (name "unconnected-(U2-PadRUN)") (class "Default")
      (node (ref "U2") (pin "RUN") (pinfunction "RUN_RUN") (pintype "bidirectional"))
    )
    (net (code "115") (name "unconnected-(U2-PadVBUS)") (class "Default")
      (node (ref "U2") (pin "VBUS") (pinfunction "VBUS_VBUS") (pintype "bidirectional"))
    )
    (net (code "116") (name "unconnected-(U3-Pad3V3)") (class "Default")
      (node (ref "U3") (pin "3V3") (pinfunction "3V3_3V3") (pintype "bidirectional"))
    )
    (net (code "117") (name "unconnected-(U3-Pad3V3_EN)") (class "Default")
      (node (ref "U3") (pin "3V3_EN") (pinfunction "3V3_EN_3V3_EN") (pintype "bidirectional"))
    )
    (net (code "118") (name "unconnected-(U3-PadADC_VREF)") (class "Default")
      (node (ref "U3") (pin "ADC_VREF") (pinfunction "ADC_VREF_ADC_VREF") (pintype "bidirectional"))
    )
    (net (code "119") (name "unconnected-(U3-PadGP6)") (class "Default")
      (node (ref "U3") (pin "GP6") (pinfunction "GP6_GP6") (pintype "bidirectional"))
    )
    (net (code "120") (name "unconnected-(U3-PadGP7)") (class "Default")
      (node (ref "U3") (pin "GP7") (pinfunction "GP7_GP7") (pintype "bidirectional"))
    )
    (net (code "121") (name "unconnected-(U3-PadGP27_A1)") (class "Default")
      (node (ref "U3") (pin "GP27_A1") (pinfunction "GP27_A1_GP27_A1") (pintype "bidirectional"))
    )
    (net (code "122") (name "unconnected-(U3-PadGP28_A2)") (class "Default")
      (node (ref "U3") (pin "GP28_A2") (pinfunction "GP28_A2_GP28_A2") (pintype "bidirectional"))
    )
    (net (code "123") (name "unconnected-(U3-PadRUN)") (class "Default")
      (node (ref "U3") (pin "RUN") (pinfunction "RUN_RUN") (pintype "bidirectional"))
    )
    (net (code "124") (name "unconnected-(U3-PadVBUS)") (class "Default")
      (node (ref "U3") (pin "VBUS") (pinfunction "VBUS_VBUS") (pintype "bidirectional"))
    )
  )
)
